# EEM_DIOT_connector.net
KiCad netlist of a schematic drawn in Altium Designer
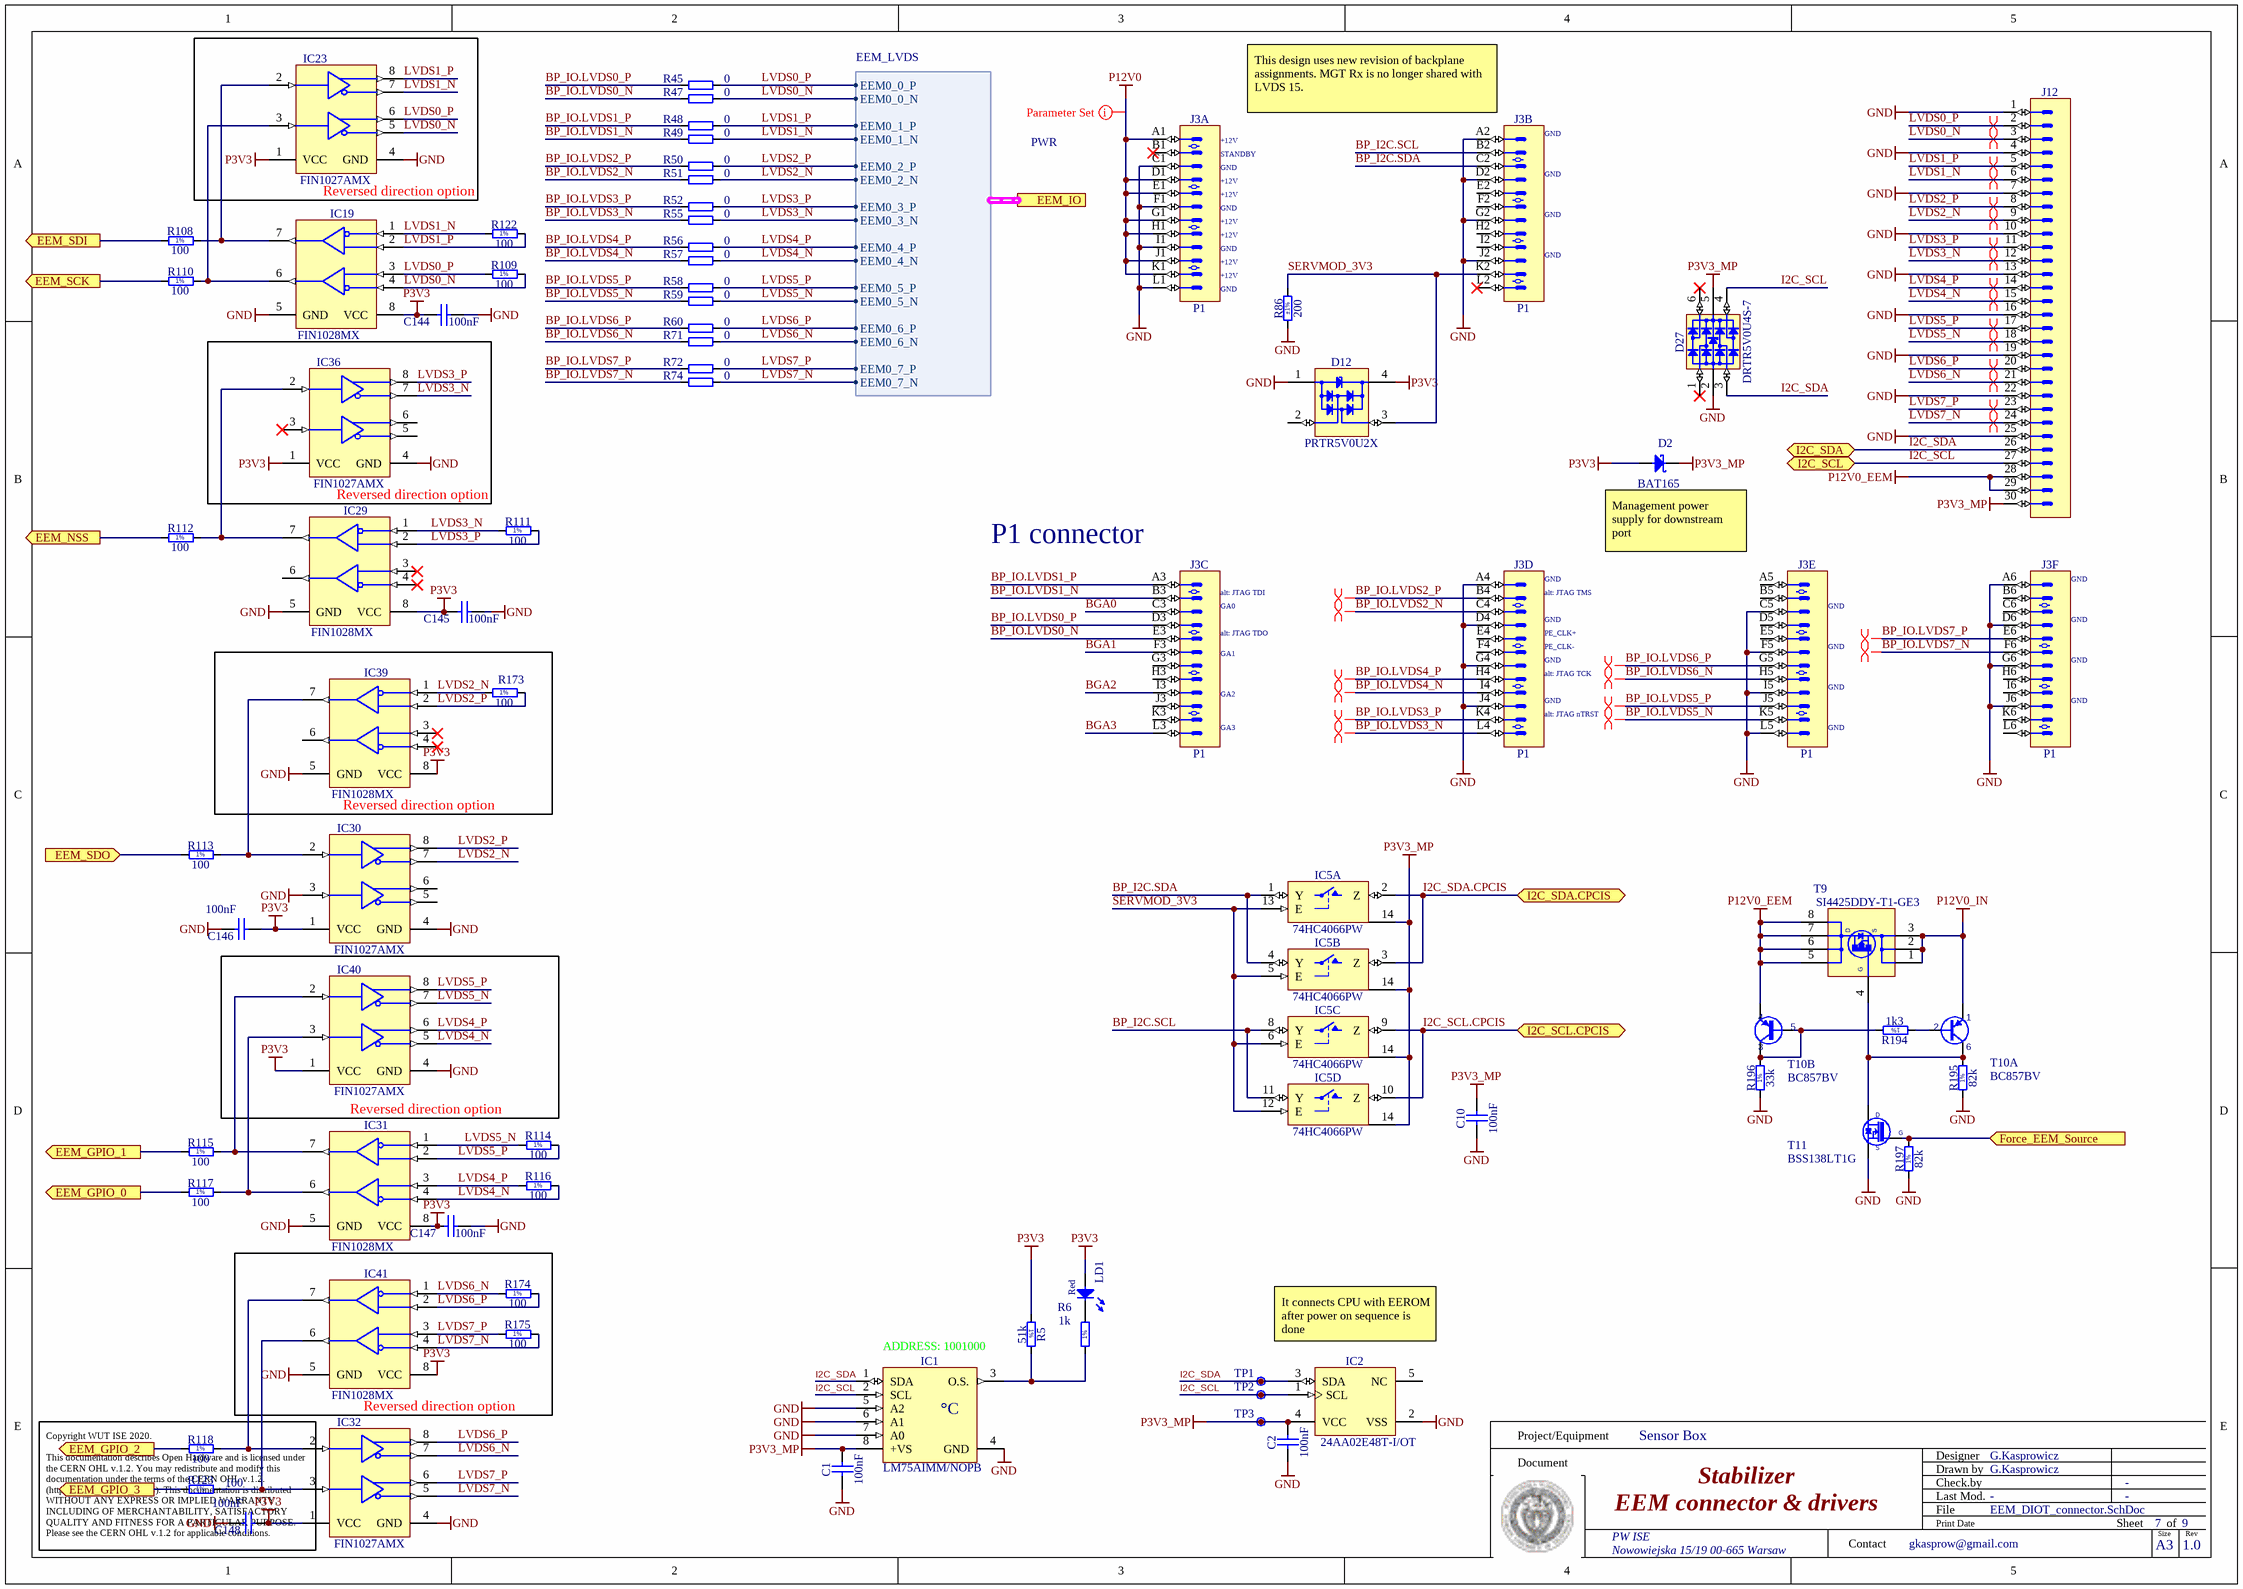
[diagram p0: EEM_DIOT_connector.SchDoc]

(export (version "E")
  (design (tool "Eeschema 10.0.6"))
  (components
    (comp (ref "C1")
      (value "100nF")
      (footprint "CAPC1005X55N")
      (description "Non-polarised capacitor")
      (fields (field (name "PART NUMBER") "CC0402_100NF_16V_10%_X5R") (field (name "VOLTAGE") "16V"))
      (libsource (lib "Capacitors") (part "Capacitor - non polarized"))
    )
    (comp (ref "C2")
      (value "100nF")
      (footprint "CAPC1005X55N")
      (description "Non-polarised capacitor")
      (fields (field (name "PART NUMBER") "CC0402_100NF_16V_10%_X5R") (field (name "VOLTAGE") "16V"))
      (libsource (lib "Capacitors") (part "Capacitor - non polarized"))
    )
    (comp (ref "C10")
      (value "100nF")
      (footprint "CAPC1608X87N")
      (description "Non-polarised capacitor")
      (fields (field (name "PART NUMBER") "CC0603_100NF_50V_10%_X7R") (field (name "VOLTAGE") "50V"))
      (libsource (lib "Capacitors") (part "Capacitor - non polarized"))
    )
    (comp (ref "C144")
      (value "100nF")
      (footprint "CAPC1005X55N")
      (description "Non-polarised capacitor")
      (fields (field (name "PART NUMBER") "CC0402_100NF_16V_10%_X5R") (field (name "VOLTAGE") "16V"))
      (libsource (lib "Capacitors") (part "Capacitor - non polarized"))
    )
    (comp (ref "C145")
      (value "100nF")
      (footprint "CAPC1005X55N")
      (description "Non-polarised capacitor")
      (fields (field (name "PART NUMBER") "CC0402_100NF_16V_10%_X5R") (field (name "VOLTAGE") "16V"))
      (libsource (lib "Capacitors") (part "Capacitor - non polarized"))
    )
    (comp (ref "C146")
      (value "100nF")
      (footprint "CAPC1005X55N")
      (description "Non-polarised capacitor")
      (fields (field (name "PART NUMBER") "CC0402_100NF_16V_10%_X5R") (field (name "VOLTAGE") "16V"))
      (libsource (lib "Capacitors") (part "Capacitor - non polarized"))
    )
    (comp (ref "C147")
      (value "100nF")
      (footprint "CAPC1005X55N")
      (description "Non-polarised capacitor")
      (fields (field (name "PART NUMBER") "CC0402_100NF_16V_10%_X5R") (field (name "VOLTAGE") "16V"))
      (libsource (lib "Capacitors") (part "Capacitor - non polarized"))
    )
    (comp (ref "C148")
      (value "100nF")
      (footprint "CAPC1005X55N")
      (description "Non-polarised capacitor")
      (fields (field (name "PART NUMBER") "CC0402_100NF_16V_10%_X5R") (field (name "VOLTAGE") "16V"))
      (libsource (lib "Capacitors") (part "Capacitor - non polarized"))
    )
    (comp (ref "D2")
      (value "BAT165")
      (footprint "SOD2512X110N")
      (description "Schottky Diode")
      (fields (field (name "VOLTAGE") "40V") (field (name "POWER") "750mA"))
      (libsource (lib "ICs And Semiconductors") (part "Diode Schottky"))
    )
    (comp (ref "D12")
      (value "PRTR5V0U2X")
      (footprint "SOT190P230X110-4N")
      (description "Ultra Low Capacitance Double Rail-to-Rail ESD Protection Diode")
      (fields (field (name "VOLTAGE") "5.5V") (field (name "MANUFACTURER") "NXP SEMICONDUCTORS"))
      (libsource (lib "ICs And Semiconductors") (part "PRTR5V0U2X"))
    )
    (comp (ref "D27")
      (value "DRTR5V0U4S-7")
      (footprint "SOT65P210X110-6N")
      (description "Integrated Quad Ultra-Low Capacitance ESD Protection")
      (fields (field (name "MANUFACTURER") "DIODES"))
      (libsource (lib "Diodes") (part "D_TVS_DRTR5V0U4S-7"))
    )
    (comp (ref "IC1")
      (value "LM75AIMM/NOPB")
      (footprint "SOP65P490X109-8N")
      (description "Digital Temperature Sensor and Thermal Watchdog with Two-Wire Interface")
      (fields (field (name "MANUFACTURER") "TEXAS INSTRUMENTS"))
      (libsource (lib "ICs And Semiconductors") (part "LM75"))
    )
    (comp (ref "IC2")
      (value "24AA02E48T-I/OT")
      (footprint "SOT95P280X145-5N")
      (description "1.7V-5.5V, 2K I2C Serial EEPROM With EUI-48 Node Identity")
      (fields (field (name "MANUFACTURER") "MICROCHIP TECHNOLOGY"))
      (libsource (lib "ICs And Semiconductors") (part "24AA02E48T-I/OT"))
    )
    (comp (ref "IC5")
      (value "74HC4066PW")
      (footprint "SOP65P640X110-14N")
      (fields (field (name "MANUFACTURER") "NXP SEMICONDUCTORS"))
      (libsource (lib "ICs And Semiconductors") (part "4066"))
    )
    (comp (ref "IC19")
      (value "FIN1028MX")
      (footprint "SOIC127P600X175-8N")
      (description "3.3V LVDS 2-Bit High-Speed Differential Reciever")
      (fields (field (name "MANUFACTURER") "ON Semiconductor"))
      (libsource (lib "LIBRARY_SCH") (part "IFC_FIN1028"))
    )
    (comp (ref "IC23")
      (value "FIN1027AMX")
      (footprint "SOIC127P600X175-8N")
      (description "3.3V LVDS, 2-Bit, High-Speed, Differential Driver")
      (fields (field (name "MANUFACTURER") "ON Semiconductor"))
      (libsource (lib "LIBRARY_SCH") (part "IFC_FIN1027A"))
    )
    (comp (ref "IC29")
      (value "FIN1028MX")
      (footprint "SOIC127P600X175-8N")
      (description "3.3V LVDS 2-Bit High-Speed Differential Reciever")
      (fields (field (name "MANUFACTURER") "ON Semiconductor"))
      (libsource (lib "LIBRARY_SCH") (part "IFC_FIN1028"))
    )
    (comp (ref "IC30")
      (value "FIN1027AMX")
      (footprint "SOIC127P600X175-8N")
      (description "3.3V LVDS, 2-Bit, High-Speed, Differential Driver")
      (fields (field (name "MANUFACTURER") "ON Semiconductor"))
      (libsource (lib "LIBRARY_SCH") (part "IFC_FIN1027A"))
    )
    (comp (ref "IC31")
      (value "FIN1028MX")
      (footprint "SOIC127P600X175-8N")
      (description "3.3V LVDS 2-Bit High-Speed Differential Reciever")
      (fields (field (name "MANUFACTURER") "ON Semiconductor"))
      (libsource (lib "LIBRARY_SCH") (part "IFC_FIN1028"))
    )
    (comp (ref "IC32")
      (value "FIN1027AMX")
      (footprint "SOIC127P600X175-8N")
      (description "3.3V LVDS, 2-Bit, High-Speed, Differential Driver")
      (fields (field (name "MANUFACTURER") "ON Semiconductor"))
      (libsource (lib "LIBRARY_SCH") (part "IFC_FIN1027A"))
    )
    (comp (ref "IC36")
      (value "FIN1027AMX")
      (footprint "SOIC127P600X175-8N")
      (description "3.3V LVDS, 2-Bit, High-Speed, Differential Driver")
      (fields (field (name "MANUFACTURER") "ON Semiconductor"))
      (libsource (lib "LIBRARY_SCH") (part "IFC_FIN1027A"))
    )
    (comp (ref "IC39")
      (value "FIN1028MX")
      (footprint "SOIC127P600X175-8N")
      (description "3.3V LVDS 2-Bit High-Speed Differential Reciever")
      (fields (field (name "MANUFACTURER") "ON Semiconductor"))
      (libsource (lib "LIBRARY_SCH") (part "IFC_FIN1028"))
    )
    (comp (ref "IC40")
      (value "FIN1027AMX")
      (footprint "SOIC127P600X175-8N")
      (description "3.3V LVDS, 2-Bit, High-Speed, Differential Driver")
      (fields (field (name "MANUFACTURER") "ON Semiconductor"))
      (libsource (lib "LIBRARY_SCH") (part "IFC_FIN1027A"))
    )
    (comp (ref "IC41")
      (value "FIN1028MX")
      (footprint "SOIC127P600X175-8N")
      (description "3.3V LVDS 2-Bit High-Speed Differential Reciever")
      (fields (field (name "MANUFACTURER") "ON Semiconductor"))
      (libsource (lib "LIBRARY_SCH") (part "IFC_FIN1028"))
    )
    (comp (ref "J3")
      (value "P1")
      (footprint "AMPHENOL_10052825-101LF")
      (description "72 Contacts Header, 6 Columns, 4 Pairs per Column")
      (fields (field (name "PART NUMBER") "AMPHENOL_10052825-101LF") (field (name "MANUFACTURER") "AMPHENOL"))
      (libsource (lib "Connectors") (part "AMPHENOL_10052825-101LF"))
    )
    (comp (ref "J12")
      (value "~")
      (footprint "3M_N2530-6002RB")
      (description "Connector 30 Male")
      (fields (field (name "PART NUMBER") "3M_N2530-6002RB") (field (name "MANUFACTURER") "3M"))
      (libsource (lib "Connectors") (part "Connector 30 Male"))
    )
    (comp (ref "LD1")
      (value "Red")
      (footprint "LED_KINGBRIGHT_KPH-1608SURCK")
      (description "LED Red 1C 2A")
      (fields
        (field (name "PART NUMBER") "LED_KINGBRIGHT_KPH-1608SURCK")
        (field (name "MANUFACTURER") "KINGBRIGHT")
      )
      (libsource (lib "ICs And Semiconductors") (part "LED Red 1C 2A"))
    )
    (comp (ref "R5")
      (value "51k")
      (footprint "RESC1005X40N")
      (description "Resistor - 1%")
      (fields (field (name "PART NUMBER") "R0402_51K_1%_0.0625W_100PPM") (field (name "POWER") "0.0625W"))
      (libsource (lib "Resistors") (part "Resistor - 1%"))
    )
    (comp (ref "R6")
      (value "1k")
      (footprint "RESC1005X40N")
      (description "Resistor - 1%")
      (fields (field (name "PART NUMBER") "R0402_1K_1%_0.0625W_100PPM") (field (name "POWER") "0.0625W"))
      (libsource (lib "Resistors") (part "Resistor - 1%"))
    )
    (comp (ref "R45")
      (value "0")
      (footprint "RESC1608X55N")
      (description "Resistor")
      (fields (field (name "PART NUMBER") "R0603_0R_JUMPER") (field (name "MANUFACTURER") "GENERIC"))
      (libsource (lib "Resistors") (part "Resistor"))
    )
    (comp (ref "R47")
      (value "0")
      (footprint "RESC1608X55N")
      (description "Resistor")
      (fields (field (name "PART NUMBER") "R0603_0R_JUMPER") (field (name "MANUFACTURER") "GENERIC"))
      (libsource (lib "Resistors") (part "Resistor"))
    )
    (comp (ref "R48")
      (value "0")
      (footprint "RESC1608X55N")
      (description "Resistor")
      (fields (field (name "PART NUMBER") "R0603_0R_JUMPER") (field (name "MANUFACTURER") "GENERIC"))
      (libsource (lib "Resistors") (part "Resistor"))
    )
    (comp (ref "R49")
      (value "0")
      (footprint "RESC1608X55N")
      (description "Resistor")
      (fields (field (name "PART NUMBER") "R0603_0R_JUMPER") (field (name "MANUFACTURER") "GENERIC"))
      (libsource (lib "Resistors") (part "Resistor"))
    )
    (comp (ref "R50")
      (value "0")
      (footprint "RESC1608X55N")
      (description "Resistor")
      (fields (field (name "PART NUMBER") "R0603_0R_JUMPER") (field (name "MANUFACTURER") "GENERIC"))
      (libsource (lib "Resistors") (part "Resistor"))
    )
    (comp (ref "R51")
      (value "0")
      (footprint "RESC1608X55N")
      (description "Resistor")
      (fields (field (name "PART NUMBER") "R0603_0R_JUMPER") (field (name "MANUFACTURER") "GENERIC"))
      (libsource (lib "Resistors") (part "Resistor"))
    )
    (comp (ref "R52")
      (value "0")
      (footprint "RESC1608X55N")
      (description "Resistor")
      (fields (field (name "PART NUMBER") "R0603_0R_JUMPER") (field (name "MANUFACTURER") "GENERIC"))
      (libsource (lib "Resistors") (part "Resistor"))
    )
    (comp (ref "R55")
      (value "0")
      (footprint "RESC1608X55N")
      (description "Resistor")
      (fields (field (name "PART NUMBER") "R0603_0R_JUMPER") (field (name "MANUFACTURER") "GENERIC"))
      (libsource (lib "Resistors") (part "Resistor"))
    )
    (comp (ref "R56")
      (value "0")
      (footprint "RESC1608X55N")
      (description "Resistor")
      (fields (field (name "PART NUMBER") "R0603_0R_JUMPER") (field (name "MANUFACTURER") "GENERIC"))
      (libsource (lib "Resistors") (part "Resistor"))
    )
    (comp (ref "R57")
      (value "0")
      (footprint "RESC1608X55N")
      (description "Resistor")
      (fields (field (name "PART NUMBER") "R0603_0R_JUMPER") (field (name "MANUFACTURER") "GENERIC"))
      (libsource (lib "Resistors") (part "Resistor"))
    )
    (comp (ref "R58")
      (value "0")
      (footprint "RESC1608X55N")
      (description "Resistor")
      (fields (field (name "PART NUMBER") "R0603_0R_JUMPER") (field (name "MANUFACTURER") "GENERIC"))
      (libsource (lib "Resistors") (part "Resistor"))
    )
    (comp (ref "R59")
      (value "0")
      (footprint "RESC1608X55N")
      (description "Resistor")
      (fields (field (name "PART NUMBER") "R0603_0R_JUMPER") (field (name "MANUFACTURER") "GENERIC"))
      (libsource (lib "Resistors") (part "Resistor"))
    )
    (comp (ref "R60")
      (value "0")
      (footprint "RESC1608X55N")
      (description "Resistor")
      (fields (field (name "PART NUMBER") "R0603_0R_JUMPER") (field (name "MANUFACTURER") "GENERIC"))
      (libsource (lib "Resistors") (part "Resistor"))
    )
    (comp (ref "R71")
      (value "0")
      (footprint "RESC1608X55N")
      (description "Resistor")
      (fields (field (name "PART NUMBER") "R0603_0R_JUMPER") (field (name "MANUFACTURER") "GENERIC"))
      (libsource (lib "Resistors") (part "Resistor"))
    )
    (comp (ref "R72")
      (value "0")
      (footprint "RESC1608X55N")
      (description "Resistor")
      (fields (field (name "PART NUMBER") "R0603_0R_JUMPER") (field (name "MANUFACTURER") "GENERIC"))
      (libsource (lib "Resistors") (part "Resistor"))
    )
    (comp (ref "R74")
      (value "0")
      (footprint "RESC1608X55N")
      (description "Resistor")
      (fields (field (name "PART NUMBER") "R0603_0R_JUMPER") (field (name "MANUFACTURER") "GENERIC"))
      (libsource (lib "Resistors") (part "Resistor"))
    )
    (comp (ref "R86")
      (value "200")
      (footprint "RESC1608X55N")
      (description "Resistor - 1%")
      (fields
        (field (name "TOLERANCE") "±1%")
        (field (name "PART NUMBER") "R0603_200R_1%_0.1W_100PPM")
        (field (name "POWER") "0.1W")
      )
      (libsource (lib "") (part "Resistor - 1%_1"))
    )
    (comp (ref "R108")
      (value "100")
      (footprint "RESC1005X40N")
      (description "Resistor - 1%")
      (fields (field (name "PART NUMBER") "R0402_100R_1%_0.0625W_100PPM") (field (name "POWER") "0.0625W"))
      (libsource (lib "Resistors") (part "Resistor - 1%"))
    )
    (comp (ref "R109")
      (value "100")
      (footprint "RESC1005X40N")
      (description "Resistor - 1%")
      (fields (field (name "PART NUMBER") "R0402_100R_1%_0.0625W_100PPM") (field (name "POWER") "0.0625W"))
      (libsource (lib "Resistors") (part "Resistor - 1%"))
    )
    (comp (ref "R110")
      (value "100")
      (footprint "RESC1005X40N")
      (description "Resistor - 1%")
      (fields (field (name "PART NUMBER") "R0402_100R_1%_0.0625W_100PPM") (field (name "POWER") "0.0625W"))
      (libsource (lib "Resistors") (part "Resistor - 1%"))
    )
    (comp (ref "R111")
      (value "100")
      (footprint "RESC1005X40N")
      (description "Resistor - 1%")
      (fields (field (name "PART NUMBER") "R0402_100R_1%_0.0625W_100PPM") (field (name "POWER") "0.0625W"))
      (libsource (lib "Resistors") (part "Resistor - 1%"))
    )
    (comp (ref "R112")
      (value "100")
      (footprint "RESC1005X40N")
      (description "Resistor - 1%")
      (fields (field (name "PART NUMBER") "R0402_100R_1%_0.0625W_100PPM") (field (name "POWER") "0.0625W"))
      (libsource (lib "Resistors") (part "Resistor - 1%"))
    )
    (comp (ref "R113")
      (value "100")
      (footprint "RESC1005X40N")
      (description "Resistor - 1%")
      (fields (field (name "PART NUMBER") "R0402_100R_1%_0.0625W_100PPM") (field (name "POWER") "0.0625W"))
      (libsource (lib "Resistors") (part "Resistor - 1%"))
    )
    (comp (ref "R114")
      (value "100")
      (footprint "RESC1005X40N")
      (description "Resistor - 1%")
      (fields (field (name "PART NUMBER") "R0402_100R_1%_0.0625W_100PPM") (field (name "POWER") "0.0625W"))
      (libsource (lib "Resistors") (part "Resistor - 1%"))
    )
    (comp (ref "R115")
      (value "100")
      (footprint "RESC1005X40N")
      (description "Resistor - 1%")
      (fields (field (name "PART NUMBER") "R0402_100R_1%_0.0625W_100PPM") (field (name "POWER") "0.0625W"))
      (libsource (lib "Resistors") (part "Resistor - 1%"))
    )
    (comp (ref "R116")
      (value "100")
      (footprint "RESC1005X40N")
      (description "Resistor - 1%")
      (fields (field (name "PART NUMBER") "R0402_100R_1%_0.0625W_100PPM") (field (name "POWER") "0.0625W"))
      (libsource (lib "Resistors") (part "Resistor - 1%"))
    )
    (comp (ref "R117")
      (value "100")
      (footprint "RESC1005X40N")
      (description "Resistor - 1%")
      (fields (field (name "PART NUMBER") "R0402_100R_1%_0.0625W_100PPM") (field (name "POWER") "0.0625W"))
      (libsource (lib "Resistors") (part "Resistor - 1%"))
    )
    (comp (ref "R118")
      (value "100")
      (footprint "RESC1005X40N")
      (description "Resistor - 1%")
      (fields (field (name "PART NUMBER") "R0402_100R_1%_0.0625W_100PPM") (field (name "POWER") "0.0625W"))
      (libsource (lib "Resistors") (part "Resistor - 1%"))
    )
    (comp (ref "R122")
      (value "100")
      (footprint "RESC1005X40N")
      (description "Resistor - 1%")
      (fields (field (name "PART NUMBER") "R0402_100R_1%_0.0625W_100PPM") (field (name "POWER") "0.0625W"))
      (libsource (lib "Resistors") (part "Resistor - 1%"))
    )
    (comp (ref "R123")
      (value "100")
      (footprint "RESC1005X40N")
      (description "Resistor - 1%")
      (fields (field (name "PART NUMBER") "R0402_100R_1%_0.0625W_100PPM") (field (name "POWER") "0.0625W"))
      (libsource (lib "Resistors") (part "Resistor - 1%"))
    )
    (comp (ref "R173")
      (value "100")
      (footprint "RESC1005X40N")
      (description "Resistor - 1%")
      (fields (field (name "PART NUMBER") "R0402_100R_1%_0.0625W_100PPM") (field (name "POWER") "0.0625W"))
      (libsource (lib "Resistors") (part "Resistor - 1%"))
    )
    (comp (ref "R174")
      (value "100")
      (footprint "RESC1005X40N")
      (description "Resistor - 1%")
      (fields (field (name "PART NUMBER") "R0402_100R_1%_0.0625W_100PPM") (field (name "POWER") "0.0625W"))
      (libsource (lib "Resistors") (part "Resistor - 1%"))
    )
    (comp (ref "R175")
      (value "100")
      (footprint "RESC1005X40N")
      (description "Resistor - 1%")
      (fields (field (name "PART NUMBER") "R0402_100R_1%_0.0625W_100PPM") (field (name "POWER") "0.0625W"))
      (libsource (lib "Resistors") (part "Resistor - 1%"))
    )
    (comp (ref "R194")
      (value "1k3")
      (footprint "RESC1608X55N")
      (description "Resistor - 1%")
      (fields (field (name "PART NUMBER") "R0603_1K3_1%_0.1W_100PPM") (field (name "POWER") "0.1W"))
      (libsource (lib "Resistors") (part "Resistor - 1%"))
    )
    (comp (ref "R195")
      (value "82k")
      (footprint "RESC1608X55N")
      (description "Resistor - 1%")
      (fields (field (name "PART NUMBER") "R0603_82K_1%_0.1W_100PPM") (field (name "POWER") "0.1W"))
      (libsource (lib "Resistors") (part "Resistor - 1%"))
    )
    (comp (ref "R196")
      (value "33k")
      (footprint "RESC1005X40N")
      (description "Resistor - 1%")
      (fields (field (name "PART NUMBER") "R0402_33K_1%_0.0625W_100PPM") (field (name "POWER") "0.0625W"))
      (libsource (lib "Resistors") (part "Resistor - 1%"))
    )
    (comp (ref "R197")
      (value "82k")
      (footprint "RESC1608X55N")
      (description "Resistor - 1%")
      (fields (field (name "PART NUMBER") "R0603_82K_1%_0.1W_100PPM") (field (name "POWER") "0.1W"))
      (libsource (lib "Resistors") (part "Resistor - 1%"))
    )
    (comp (ref "T9")
      (value "SI4425DDY-T1-GE3")
      (footprint "SOIC127P600X175-8N")
      (description "-30V -19.7A P-Channel MOSFET")
      (fields (field (name "MANUFACTURER") "VISHAY SILICONIX"))
      (libsource (lib "ICs And Semiconductors") (part "SI4425DDY"))
    )
    (comp (ref "T10")
      (value "BC857BV")
      (footprint "SOTFL50P160X60-6N")
      (description "45V, 100mA PNP General Purpose Double Transistor")
      (fields (field (name "MANUFACTURER") "NXP SEMICONDUCTORS"))
      (libsource (lib "ICs And Semiconductors") (part "BC857BV"))
    )
    (comp (ref "T11")
      (value "BSS138LT1G")
      (footprint "SOT95P240X110-3N")
      (description "N-CHANNEL MOSFET WITH DIODE")
      (fields (field (name "MANUFACTURER") "ON SEMICONDUCTOR"))
      (libsource (lib "ICs And Semiconductors") (part "N-MOSFET-D 1G 2S 3D"))
    )
    (comp (ref "TP1")
      (value "Test Point")
      (footprint "TPS127")
      (fields (field (name "PART NUMBER") "SMD_PAD_1.27X1.27MM"))
      (libsource (lib "Eletro-mechanical") (part "Test Point"))
    )
    (comp (ref "TP2")
      (value "Test Point")
      (footprint "TPS127")
      (fields (field (name "PART NUMBER") "SMD_PAD_1.27X1.27MM"))
      (libsource (lib "Eletro-mechanical") (part "Test Point"))
    )
    (comp (ref "TP3")
      (value "Test Point")
      (footprint "TPS127")
      (fields (field (name "PART NUMBER") "SMD_PAD_1.27X1.27MM"))
      (libsource (lib "Eletro-mechanical") (part "Test Point"))
    )
  )
  (nets
    (net (code "2") (name "/BGA0") (class "Default")
      (node (ref "J3") (pin "C3") (pinfunction "C3_C3") (pintype "bidirectional"))
    )
    (net (code "3") (name "/BGA1") (class "Default")
      (node (ref "J3") (pin "F3") (pinfunction "F3_F3") (pintype "bidirectional"))
    )
    (net (code "4") (name "/BGA2") (class "Default")
      (node (ref "J3") (pin "I3") (pinfunction "I3_I3") (pintype "bidirectional"))
    )
    (net (code "5") (name "/BGA3") (class "Default")
      (node (ref "J3") (pin "L3") (pinfunction "L3_L3") (pintype "bidirectional"))
    )
    (net (code "6") (name "/BP_I2C.SCL") (class "Default")
      (node (ref "IC5") (pin "11") (pinfunction "Y_11") (pintype "bidirectional"))
      (node (ref "IC5") (pin "8") (pinfunction "Y_8") (pintype "bidirectional"))
      (node (ref "J3") (pin "B2") (pinfunction "B2_B2") (pintype "bidirectional"))
    )
    (net (code "7") (name "/BP_I2C.SDA") (class "Default")
      (node (ref "IC5") (pin "1") (pinfunction "Y_1") (pintype "bidirectional"))
      (node (ref "IC5") (pin "4") (pinfunction "Y_4") (pintype "bidirectional"))
      (node (ref "J3") (pin "C2") (pinfunction "C2_C2") (pintype "bidirectional"))
    )
    (net (code "8") (name "/BP_IO.LVDS0_N") (class "Default")
      (node (ref "J3") (pin "E3") (pinfunction "E3_E3") (pintype "bidirectional"))
      (node (ref "R47") (pin "1") (pinfunction "1_1") (pintype "passive"))
    )
    (net (code "9") (name "/BP_IO.LVDS0_P") (class "Default")
      (node (ref "J3") (pin "D3") (pinfunction "D3_D3") (pintype "bidirectional"))
      (node (ref "R45") (pin "1") (pinfunction "1_1") (pintype "passive"))
    )
    (net (code "10") (name "/BP_IO.LVDS1_N") (class "Default")
      (node (ref "J3") (pin "B3") (pinfunction "B3_B3") (pintype "bidirectional"))
      (node (ref "R49") (pin "1") (pinfunction "1_1") (pintype "passive"))
    )
    (net (code "11") (name "/BP_IO.LVDS1_P") (class "Default")
      (node (ref "J3") (pin "A3") (pinfunction "A3_A3") (pintype "bidirectional"))
      (node (ref "R48") (pin "1") (pinfunction "1_1") (pintype "passive"))
    )
    (net (code "12") (name "/BP_IO.LVDS2_N") (class "Default")
      (node (ref "J3") (pin "C4") (pinfunction "C4_C4") (pintype "bidirectional"))
      (node (ref "R51") (pin "1") (pinfunction "1_1") (pintype "passive"))
    )
    (net (code "13") (name "/BP_IO.LVDS2_P") (class "Default")
      (node (ref "J3") (pin "B4") (pinfunction "B4_B4") (pintype "bidirectional"))
      (node (ref "R50") (pin "1") (pinfunction "1_1") (pintype "passive"))
    )
    (net (code "14") (name "/BP_IO.LVDS3_N") (class "Default")
      (node (ref "J3") (pin "L4") (pinfunction "L4_L4") (pintype "bidirectional"))
      (node (ref "R55") (pin "1") (pinfunction "1_1") (pintype "passive"))
    )
    (net (code "15") (name "/BP_IO.LVDS3_P") (class "Default")
      (node (ref "J3") (pin "K4") (pinfunction "K4_K4") (pintype "bidirectional"))
      (node (ref "R52") (pin "1") (pinfunction "1_1") (pintype "passive"))
    )
    (net (code "16") (name "/BP_IO.LVDS4_N") (class "Default")
      (node (ref "J3") (pin "I4") (pinfunction "I4_I4") (pintype "bidirectional"))
      (node (ref "R57") (pin "1") (pinfunction "1_1") (pintype "passive"))
    )
    (net (code "17") (name "/BP_IO.LVDS4_P") (class "Default")
      (node (ref "J3") (pin "H4") (pinfunction "H4_H4") (pintype "bidirectional"))
      (node (ref "R56") (pin "1") (pinfunction "1_1") (pintype "passive"))
    )
    (net (code "18") (name "/BP_IO.LVDS5_N") (class "Default")
      (node (ref "J3") (pin "K5") (pinfunction "K5_K5") (pintype "bidirectional"))
      (node (ref "R59") (pin "1") (pinfunction "1_1") (pintype "passive"))
    )
    (net (code "19") (name "/BP_IO.LVDS5_P") (class "Default")
      (node (ref "J3") (pin "J5") (pinfunction "J5_J5") (pintype "bidirectional"))
      (node (ref "R58") (pin "1") (pinfunction "1_1") (pintype "passive"))
    )
    (net (code "20") (name "/BP_IO.LVDS6_N") (class "Default")
      (node (ref "J3") (pin "H5") (pinfunction "H5_H5") (pintype "bidirectional"))
      (node (ref "R71") (pin "1") (pinfunction "1_1") (pintype "passive"))
    )
    (net (code "21") (name "/BP_IO.LVDS6_P") (class "Default")
      (node (ref "J3") (pin "G5") (pinfunction "G5_G5") (pintype "bidirectional"))
      (node (ref "R60") (pin "1") (pinfunction "1_1") (pintype "passive"))
    )
    (net (code "22") (name "/BP_IO.LVDS7_N") (class "Default")
      (node (ref "J3") (pin "F6") (pinfunction "F6_F6") (pintype "bidirectional"))
      (node (ref "R74") (pin "1") (pinfunction "1_1") (pintype "passive"))
    )
    (net (code "23") (name "/BP_IO.LVDS7_P") (class "Default")
      (node (ref "J3") (pin "E6") (pinfunction "E6_E6") (pintype "bidirectional"))
      (node (ref "R72") (pin "1") (pinfunction "1_1") (pintype "passive"))
    )
    (net (code "24") (name "/EEM_GPIO_0") (class "Default")
      (node (ref "R117") (pin "1") (pinfunction "1_1") (pintype "passive"))
    )
    (net (code "25") (name "/EEM_GPIO_1") (class "Default")
      (node (ref "R115") (pin "1") (pinfunction "1_1") (pintype "passive"))
    )
    (net (code "26") (name "/EEM_GPIO_2") (class "Default")
      (node (ref "R118") (pin "1") (pinfunction "1_1") (pintype "passive"))
    )
    (net (code "27") (name "/EEM_GPIO_3") (class "Default")
      (node (ref "R123") (pin "1") (pinfunction "1_1") (pintype "passive"))
    )
    (net (code "28") (name "/EEM_NSS") (class "Default")
      (node (ref "R112") (pin "1") (pinfunction "1_1") (pintype "passive"))
    )
    (net (code "29") (name "/EEM_SCK") (class "Default")
      (node (ref "R110") (pin "1") (pinfunction "1_1") (pintype "passive"))
    )
    (net (code "30") (name "/EEM_SDI") (class "Default")
      (node (ref "R108") (pin "1") (pinfunction "1_1") (pintype "passive"))
    )
    (net (code "31") (name "/EEM_SDO") (class "Default")
      (node (ref "R113") (pin "1") (pinfunction "1_1") (pintype "passive"))
    )
    (net (code "32") (name "/Force_EEM_Source") (class "Default")
      (node (ref "R197") (pin "2") (pinfunction "2_2") (pintype "passive"))
      (node (ref "T11") (pin "1") (pinfunction "G_1") (pintype "passive"))
    )
    (net (code "33") (name "/I2C_SCL") (class "Default")
      (node (ref "D27") (pin "4") (pinfunction "I/O3_4") (pintype "bidirectional"))
      (node (ref "IC1") (pin "2") (pinfunction "SCL_2") (pintype "input"))
      (node (ref "IC2") (pin "1") (pinfunction "SCL_1") (pintype "input"))
      (node (ref "J12") (pin "27") (pinfunction "27_27") (pintype "bidirectional"))
      (node (ref "TP2") (pin "1") (pinfunction "1_1") (pintype "bidirectional"))
    )
    (net (code "34") (name "/I2C_SCL.CPCIS") (class "Default")
      (node (ref "IC5") (pin "10") (pinfunction "Z_10") (pintype "bidirectional"))
      (node (ref "IC5") (pin "9") (pinfunction "Z_9") (pintype "bidirectional"))
    )
    (net (code "35") (name "/I2C_SDA") (class "Default")
      (node (ref "D27") (pin "3") (pinfunction "I/O2_3") (pintype "bidirectional"))
      (node (ref "IC1") (pin "1") (pinfunction "SDA_1") (pintype "bidirectional"))
      (node (ref "IC2") (pin "3") (pinfunction "SDA_3") (pintype "bidirectional"))
      (node (ref "J12") (pin "26") (pinfunction "26_26") (pintype "bidirectional"))
      (node (ref "TP1") (pin "1") (pinfunction "1_1") (pintype "bidirectional"))
    )
    (net (code "36") (name "/I2C_SDA.CPCIS") (class "Default")
      (node (ref "IC5") (pin "2") (pinfunction "Z_2") (pintype "bidirectional"))
      (node (ref "IC5") (pin "3") (pinfunction "Z_3") (pintype "bidirectional"))
    )
    (net (code "37") (name "/LVDS0_N") (class "Default")
      (node (ref "IC19") (pin "4") (pinfunction "RIN2-_4") (pintype "input"))
      (node (ref "IC23") (pin "5") (pinfunction "DOUT-_5") (pintype "output"))
      (node (ref "J12") (pin "3") (pinfunction "3_3") (pintype "bidirectional"))
      (node (ref "R109") (pin "2") (pinfunction "2_2") (pintype "passive"))
      (node (ref "R47") (pin "2") (pinfunction "2_2") (pintype "passive"))
    )
    (net (code "38") (name "/LVDS0_P") (class "Default")
      (node (ref "IC19") (pin "3") (pinfunction "RIN2+_3") (pintype "input"))
      (node (ref "IC23") (pin "6") (pinfunction "DOUT+_6") (pintype "output"))
      (node (ref "J12") (pin "2") (pinfunction "2_2") (pintype "bidirectional"))
      (node (ref "R109") (pin "1") (pinfunction "1_1") (pintype "passive"))
      (node (ref "R45") (pin "2") (pinfunction "2_2") (pintype "passive"))
    )
    (net (code "39") (name "/LVDS1_N") (class "Default")
      (node (ref "IC19") (pin "1") (pinfunction "RIN1-_1") (pintype "input"))
      (node (ref "IC23") (pin "7") (pinfunction "DOUT-_7") (pintype "output"))
      (node (ref "J12") (pin "6") (pinfunction "6_6") (pintype "bidirectional"))
      (node (ref "R122") (pin "1") (pinfunction "1_1") (pintype "passive"))
      (node (ref "R49") (pin "2") (pinfunction "2_2") (pintype "passive"))
    )
    (net (code "40") (name "/LVDS1_P") (class "Default")
      (node (ref "IC19") (pin "2") (pinfunction "RIN1+_2") (pintype "input"))
      (node (ref "IC23") (pin "8") (pinfunction "DOUT+_8") (pintype "output"))
      (node (ref "J12") (pin "5") (pinfunction "5_5") (pintype "bidirectional"))
      (node (ref "R122") (pin "2") (pinfunction "2_2") (pintype "passive"))
      (node (ref "R48") (pin "2") (pinfunction "2_2") (pintype "passive"))
    )
    (net (code "41") (name "/LVDS2_N") (class "Default")
      (node (ref "IC30") (pin "7") (pinfunction "DOUT-_7") (pintype "output"))
      (node (ref "IC39") (pin "1") (pinfunction "RIN1-_1") (pintype "input"))
      (node (ref "J12") (pin "9") (pinfunction "9_9") (pintype "bidirectional"))
      (node (ref "R173") (pin "1") (pinfunction "1_1") (pintype "passive"))
      (node (ref "R51") (pin "2") (pinfunction "2_2") (pintype "passive"))
    )
    (net (code "42") (name "/LVDS2_P") (class "Default")
      (node (ref "IC30") (pin "8") (pinfunction "DOUT+_8") (pintype "output"))
      (node (ref "IC39") (pin "2") (pinfunction "RIN1+_2") (pintype "input"))
      (node (ref "J12") (pin "8") (pinfunction "8_8") (pintype "bidirectional"))
      (node (ref "R173") (pin "2") (pinfunction "2_2") (pintype "passive"))
      (node (ref "R50") (pin "2") (pinfunction "2_2") (pintype "passive"))
    )
    (net (code "43") (name "/LVDS3_N") (class "Default")
      (node (ref "IC29") (pin "1") (pinfunction "RIN1-_1") (pintype "input"))
      (node (ref "IC36") (pin "7") (pinfunction "DOUT-_7") (pintype "output"))
      (node (ref "J12") (pin "12") (pinfunction "12_12") (pintype "bidirectional"))
      (node (ref "R111") (pin "1") (pinfunction "1_1") (pintype "passive"))
      (node (ref "R55") (pin "2") (pinfunction "2_2") (pintype "passive"))
    )
    (net (code "44") (name "/LVDS3_P") (class "Default")
      (node (ref "IC29") (pin "2") (pinfunction "RIN1+_2") (pintype "input"))
      (node (ref "IC36") (pin "8") (pinfunction "DOUT+_8") (pintype "output"))
      (node (ref "J12") (pin "11") (pinfunction "11_11") (pintype "bidirectional"))
      (node (ref "R111") (pin "2") (pinfunction "2_2") (pintype "passive"))
      (node (ref "R52") (pin "2") (pinfunction "2_2") (pintype "passive"))
    )
    (net (code "45") (name "/LVDS4_N") (class "Default")
      (node (ref "IC31") (pin "4") (pinfunction "RIN2-_4") (pintype "input"))
      (node (ref "IC40") (pin "5") (pinfunction "DOUT-_5") (pintype "output"))
      (node (ref "J12") (pin "15") (pinfunction "15_15") (pintype "bidirectional"))
      (node (ref "R116") (pin "2") (pinfunction "2_2") (pintype "passive"))
      (node (ref "R57") (pin "2") (pinfunction "2_2") (pintype "passive"))
    )
    (net (code "46") (name "/LVDS4_P") (class "Default")
      (node (ref "IC31") (pin "3") (pinfunction "RIN2+_3") (pintype "input"))
      (node (ref "IC40") (pin "6") (pinfunction "DOUT+_6") (pintype "output"))
      (node (ref "J12") (pin "14") (pinfunction "14_14") (pintype "bidirectional"))
      (node (ref "R116") (pin "1") (pinfunction "1_1") (pintype "passive"))
      (node (ref "R56") (pin "2") (pinfunction "2_2") (pintype "passive"))
    )
    (net (code "47") (name "/LVDS5_N") (class "Default")
      (node (ref "IC31") (pin "1") (pinfunction "RIN1-_1") (pintype "input"))
      (node (ref "IC40") (pin "7") (pinfunction "DOUT-_7") (pintype "output"))
      (node (ref "J12") (pin "18") (pinfunction "18_18") (pintype "bidirectional"))
      (node (ref "R114") (pin "1") (pinfunction "1_1") (pintype "passive"))
      (node (ref "R59") (pin "2") (pinfunction "2_2") (pintype "passive"))
    )
    (net (code "48") (name "/LVDS5_P") (class "Default")
      (node (ref "IC31") (pin "2") (pinfunction "RIN1+_2") (pintype "input"))
      (node (ref "IC40") (pin "8") (pinfunction "DOUT+_8") (pintype "output"))
      (node (ref "J12") (pin "17") (pinfunction "17_17") (pintype "bidirectional"))
      (node (ref "R114") (pin "2") (pinfunction "2_2") (pintype "passive"))
      (node (ref "R58") (pin "2") (pinfunction "2_2") (pintype "passive"))
    )
    (net (code "49") (name "/LVDS6_N") (class "Default")
      (node (ref "IC32") (pin "7") (pinfunction "DOUT-_7") (pintype "output"))
      (node (ref "IC41") (pin "1") (pinfunction "RIN1-_1") (pintype "input"))
      (node (ref "J12") (pin "21") (pinfunction "21_21") (pintype "bidirectional"))
      (node (ref "R174") (pin "1") (pinfunction "1_1") (pintype "passive"))
      (node (ref "R71") (pin "2") (pinfunction "2_2") (pintype "passive"))
    )
    (net (code "50") (name "/LVDS6_P") (class "Default")
      (node (ref "IC32") (pin "8") (pinfunction "DOUT+_8") (pintype "output"))
      (node (ref "IC41") (pin "2") (pinfunction "RIN1+_2") (pintype "input"))
      (node (ref "J12") (pin "20") (pinfunction "20_20") (pintype "bidirectional"))
      (node (ref "R174") (pin "2") (pinfunction "2_2") (pintype "passive"))
      (node (ref "R60") (pin "2") (pinfunction "2_2") (pintype "passive"))
    )
    (net (code "51") (name "/LVDS7_N") (class "Default")
      (node (ref "IC32") (pin "5") (pinfunction "DOUT-_5") (pintype "output"))
      (node (ref "IC41") (pin "4") (pinfunction "RIN2-_4") (pintype "input"))
      (node (ref "J12") (pin "24") (pinfunction "24_24") (pintype "bidirectional"))
      (node (ref "R175") (pin "2") (pinfunction "2_2") (pintype "passive"))
      (node (ref "R74") (pin "2") (pinfunction "2_2") (pintype "passive"))
    )
    (net (code "52") (name "/LVDS7_P") (class "Default")
      (node (ref "IC32") (pin "6") (pinfunction "DOUT+_6") (pintype "output"))
      (node (ref "IC41") (pin "3") (pinfunction "RIN2+_3") (pintype "input"))
      (node (ref "J12") (pin "23") (pinfunction "23_23") (pintype "bidirectional"))
      (node (ref "R175") (pin "1") (pinfunction "1_1") (pintype "passive"))
      (node (ref "R72") (pin "2") (pinfunction "2_2") (pintype "passive"))
    )
    (net (code "53") (name "/SERVMOD_3V3") (class "Default")
      (node (ref "D12") (pin "3") (pinfunction "I/O2_3") (pintype "bidirectional"))
      (node (ref "IC5") (pin "12") (pinfunction "E_12") (pintype "input"))
      (node (ref "IC5") (pin "13") (pinfunction "E_13") (pintype "input"))
      (node (ref "IC5") (pin "5") (pinfunction "E_5") (pintype "input"))
      (node (ref "IC5") (pin "6") (pinfunction "E_6") (pintype "input"))
      (node (ref "J3") (pin "K2") (pinfunction "K2_K2") (pintype "bidirectional"))
      (node (ref "R86") (pin "2") (pinfunction "2_2") (pintype "passive"))
    )
    (net (code "55") (name "GND") (class "Default")
      (node (ref "C1") (pin "1") (pinfunction "1_1") (pintype "passive"))
      (node (ref "C10") (pin "1") (pinfunction "1_1") (pintype "passive"))
      (node (ref "C144") (pin "1") (pinfunction "1_1") (pintype "passive"))
      (node (ref "C145") (pin "1") (pinfunction "1_1") (pintype "passive"))
      (node (ref "C146") (pin "1") (pinfunction "1_1") (pintype "passive"))
      (node (ref "C147") (pin "1") (pinfunction "1_1") (pintype "passive"))
      (node (ref "C148") (pin "1") (pinfunction "1_1") (pintype "passive"))
      (node (ref "C2") (pin "1") (pinfunction "1_1") (pintype "passive"))
      (node (ref "D12") (pin "1") (pinfunction "GND_1") (pintype "power_in"))
      (node (ref "D27") (pin "2") (pinfunction "GND_2") (pintype "power_in"))
      (node (ref "IC1") (pin "4") (pinfunction "GND_4") (pintype "power_in"))
      (node (ref "IC1") (pin "5") (pinfunction "A2_5") (pintype "input"))
      (node (ref "IC1") (pin "6") (pinfunction "A1_6") (pintype "input"))
      (node (ref "IC1") (pin "7") (pinfunction "A0_7") (pintype "input"))
      (node (ref "IC19") (pin "5") (pinfunction "GND_5") (pintype "power_in"))
      (node (ref "IC2") (pin "2") (pinfunction "VSS_2") (pintype "power_in"))
      (node (ref "IC23") (pin "4") (pinfunction "GND_4") (pintype "power_in"))
      (node (ref "IC29") (pin "5") (pinfunction "GND_5") (pintype "power_in"))
      (node (ref "IC30") (pin "3") (pinfunction "DIN2RIN-_3") (pintype "input"))
      (node (ref "IC30") (pin "4") (pinfunction "GND_4") (pintype "power_in"))
      (node (ref "IC31") (pin "5") (pinfunction "GND_5") (pintype "power_in"))
      (node (ref "IC32") (pin "4") (pinfunction "GND_4") (pintype "power_in"))
      (node (ref "IC36") (pin "4") (pinfunction "GND_4") (pintype "power_in"))
      (node (ref "IC39") (pin "5") (pinfunction "GND_5") (pintype "power_in"))
      (node (ref "IC40") (pin "4") (pinfunction "GND_4") (pintype "power_in"))
      (node (ref "IC41") (pin "5") (pinfunction "GND_5") (pintype "power_in"))
      (node (ref "IC5") (pin "7") (pinfunction "GND_7") (pintype "power_in"))
      (node (ref "J12") (pin "1") (pinfunction "1_1") (pintype "bidirectional"))
      (node (ref "J12") (pin "10") (pinfunction "10_10") (pintype "bidirectional"))
      (node (ref "J12") (pin "13") (pinfunction "13_13") (pintype "bidirectional"))
      (node (ref "J12") (pin "16") (pinfunction "16_16") (pintype "bidirectional"))
      (node (ref "J12") (pin "19") (pinfunction "19_19") (pintype "bidirectional"))
      (node (ref "J12") (pin "22") (pinfunction "22_22") (pintype "bidirectional"))
      (node (ref "J12") (pin "25") (pinfunction "25_25") (pintype "bidirectional"))
      (node (ref "J12") (pin "4") (pinfunction "4_4") (pintype "bidirectional"))
      (node (ref "J12") (pin "7") (pinfunction "7_7") (pintype "bidirectional"))
      (node (ref "J3") (pin "A2") (pinfunction "A2_A2") (pintype "bidirectional"))
      (node (ref "J3") (pin "A4") (pinfunction "A4_A4") (pintype "bidirectional"))
      (node (ref "J3") (pin "A6") (pinfunction "A6_A6") (pintype "bidirectional"))
      (node (ref "J3") (pin "C1") (pinfunction "C1_C1") (pintype "bidirectional"))
      (node (ref "J3") (pin "C5") (pinfunction "C5_C5") (pintype "bidirectional"))
      (node (ref "J3") (pin "D2") (pinfunction "D2_D2") (pintype "bidirectional"))
      (node (ref "J3") (pin "D4") (pinfunction "D4_D4") (pintype "bidirectional"))
      (node (ref "J3") (pin "D6") (pinfunction "D6_D6") (pintype "bidirectional"))
      (node (ref "J3") (pin "F1") (pinfunction "F1_F1") (pintype "bidirectional"))
      (node (ref "J3") (pin "F5") (pinfunction "F5_F5") (pintype "bidirectional"))
      (node (ref "J3") (pin "G2") (pinfunction "G2_G2") (pintype "bidirectional"))
      (node (ref "J3") (pin "G4") (pinfunction "G4_G4") (pintype "bidirectional"))
      (node (ref "J3") (pin "G6") (pinfunction "G6_G6") (pintype "bidirectional"))
      (node (ref "J3") (pin "I1") (pinfunction "I1_I1") (pintype "bidirectional"))
      (node (ref "J3") (pin "I5") (pinfunction "I5_I5") (pintype "bidirectional"))
      (node (ref "J3") (pin "J2") (pinfunction "J2_J2") (pintype "bidirectional"))
      (node (ref "J3") (pin "J4") (pinfunction "J4_J4") (pintype "bidirectional"))
      (node (ref "J3") (pin "J6") (pinfunction "J6_J6") (pintype "bidirectional"))
      (node (ref "J3") (pin "L1") (pinfunction "L1_L1") (pintype "bidirectional"))
      (node (ref "J3") (pin "L5") (pinfunction "L5_L5") (pintype "bidirectional"))
      (node (ref "R195") (pin "1") (pinfunction "1_1") (pintype "passive"))
      (node (ref "R196") (pin "1") (pinfunction "1_1") (pintype "passive"))
      (node (ref "R197") (pin "1") (pinfunction "1_1") (pintype "passive"))
      (node (ref "R86") (pin "1") (pinfunction "1_1") (pintype "passive"))
      (node (ref "T11") (pin "2") (pinfunction "S_2") (pintype "passive"))
    )
    (net (code "56") (name "Net-(IC1-O.S.)") (class "Default")
      (node (ref "IC1") (pin "3") (pinfunction "O.S._3") (pintype "output"))
      (node (ref "R5") (pin "2") (pinfunction "2_2") (pintype "passive"))
      (node (ref "R6") (pin "1") (pinfunction "1_1") (pintype "passive"))
    )
    (net (code "57") (name "Net-(IC19-ROUT1)") (class "Default")
      (node (ref "IC19") (pin "7") (pinfunction "ROUT1_7") (pintype "output"))
      (node (ref "IC23") (pin "2") (pinfunction "DIN1_2") (pintype "input"))
      (node (ref "R108") (pin "2") (pinfunction "2_2") (pintype "passive"))
    )
    (net (code "58") (name "Net-(IC19-ROUT2)") (class "Default")
      (node (ref "IC19") (pin "6") (pinfunction "ROUT2_6") (pintype "output"))
      (node (ref "IC23") (pin "3") (pinfunction "DIN2RIN-_3") (pintype "input"))
      (node (ref "R110") (pin "2") (pinfunction "2_2") (pintype "passive"))
    )
    (net (code "59") (name "Net-(IC29-ROUT1)") (class "Default")
      (node (ref "IC29") (pin "7") (pinfunction "ROUT1_7") (pintype "output"))
      (node (ref "IC36") (pin "2") (pinfunction "DIN1_2") (pintype "input"))
      (node (ref "R112") (pin "2") (pinfunction "2_2") (pintype "passive"))
    )
    (net (code "60") (name "Net-(IC30-DIN1)") (class "Default")
      (node (ref "IC30") (pin "2") (pinfunction "DIN1_2") (pintype "input"))
      (node (ref "IC39") (pin "7") (pinfunction "ROUT1_7") (pintype "output"))
      (node (ref "R113") (pin "2") (pinfunction "2_2") (pintype "passive"))
    )
    (net (code "61") (name "Net-(IC31-ROUT1)") (class "Default")
      (node (ref "IC31") (pin "7") (pinfunction "ROUT1_7") (pintype "output"))
      (node (ref "IC40") (pin "2") (pinfunction "DIN1_2") (pintype "input"))
      (node (ref "R115") (pin "2") (pinfunction "2_2") (pintype "passive"))
    )
    (net (code "62") (name "Net-(IC31-ROUT2)") (class "Default")
      (node (ref "IC31") (pin "6") (pinfunction "ROUT2_6") (pintype "output"))
      (node (ref "IC40") (pin "3") (pinfunction "DIN2RIN-_3") (pintype "input"))
      (node (ref "R117") (pin "2") (pinfunction "2_2") (pintype "passive"))
    )
    (net (code "63") (name "Net-(IC32-DIN1)") (class "Default")
      (node (ref "IC32") (pin "2") (pinfunction "DIN1_2") (pintype "input"))
      (node (ref "IC41") (pin "7") (pinfunction "ROUT1_7") (pintype "output"))
      (node (ref "R118") (pin "2") (pinfunction "2_2") (pintype "passive"))
    )
    (net (code "64") (name "Net-(IC32-DIN2RIN-)") (class "Default")
      (node (ref "IC32") (pin "3") (pinfunction "DIN2RIN-_3") (pintype "input"))
      (node (ref "IC41") (pin "6") (pinfunction "ROUT2_6") (pintype "output"))
      (node (ref "R123") (pin "2") (pinfunction "2_2") (pintype "passive"))
    )
    (net (code "65") (name "Net-(LD1-C)") (class "Default")
      (node (ref "LD1") (pin "1") (pinfunction "C_1") (pintype "passive"))
      (node (ref "R6") (pin "2") (pinfunction "2_2") (pintype "passive"))
    )
    (net (code "66") (name "Net-(T10A-B)") (class "Default")
      (node (ref "R194") (pin "1") (pinfunction "1_1") (pintype "passive"))
      (node (ref "T10") (pin "2") (pinfunction "B_2") (pintype "passive"))
    )
    (net (code "67") (name "Net-(T10A-C)") (class "Default")
      (node (ref "R195") (pin "2") (pinfunction "2_2") (pintype "passive"))
      (node (ref "T10") (pin "6") (pinfunction "C_6") (pintype "passive"))
      (node (ref "T11") (pin "3") (pinfunction "D_3") (pintype "passive"))
      (node (ref "T9") (pin "4") (pinfunction "S_4") (pintype "passive"))
    )
    (net (code "68") (name "Net-(T10B-B)") (class "Default")
      (node (ref "R194") (pin "2") (pinfunction "2_2") (pintype "passive"))
      (node (ref "R196") (pin "2") (pinfunction "2_2") (pintype "passive"))
      (node (ref "T10") (pin "3") (pinfunction "C_3") (pintype "passive"))
      (node (ref "T10") (pin "5") (pinfunction "B_5") (pintype "passive"))
    )
    (net (code "69") (name "P3V3") (class "Default")
      (node (ref "C144") (pin "2") (pinfunction "2_2") (pintype "passive"))
      (node (ref "C145") (pin "2") (pinfunction "2_2") (pintype "passive"))
      (node (ref "C146") (pin "2") (pinfunction "2_2") (pintype "passive"))
      (node (ref "C147") (pin "2") (pinfunction "2_2") (pintype "passive"))
      (node (ref "C148") (pin "2") (pinfunction "2_2") (pintype "passive"))
      (node (ref "D12") (pin "4") (pinfunction "VCC_4") (pintype "power_in"))
      (node (ref "D2") (pin "2") (pinfunction "A_2") (pintype "passive"))
      (node (ref "IC19") (pin "8") (pinfunction "VCC_8") (pintype "power_in"))
      (node (ref "IC23") (pin "1") (pinfunction "VCC_1") (pintype "power_in"))
      (node (ref "IC29") (pin "8") (pinfunction "VCC_8") (pintype "power_in"))
      (node (ref "IC30") (pin "1") (pinfunction "VCC_1") (pintype "power_in"))
      (node (ref "IC31") (pin "8") (pinfunction "VCC_8") (pintype "power_in"))
      (node (ref "IC32") (pin "1") (pinfunction "VCC_1") (pintype "power_in"))
      (node (ref "IC36") (pin "1") (pinfunction "VCC_1") (pintype "power_in"))
      (node (ref "IC39") (pin "8") (pinfunction "VCC_8") (pintype "power_in"))
      (node (ref "IC40") (pin "1") (pinfunction "VCC_1") (pintype "power_in"))
      (node (ref "IC41") (pin "8") (pinfunction "VCC_8") (pintype "power_in"))
      (node (ref "LD1") (pin "2") (pinfunction "A_2") (pintype "passive"))
      (node (ref "R5") (pin "1") (pinfunction "1_1") (pintype "passive"))
    )
    (net (code "70") (name "P3V3_MP") (class "Default")
      (node (ref "C1") (pin "2") (pinfunction "2_2") (pintype "passive"))
      (node (ref "C10") (pin "2") (pinfunction "2_2") (pintype "passive"))
      (node (ref "C2") (pin "2") (pinfunction "2_2") (pintype "passive"))
      (node (ref "D2") (pin "1") (pinfunction "C_1") (pintype "passive"))
      (node (ref "D27") (pin "5") (pinfunction "VBUS_5") (pintype "power_in"))
      (node (ref "IC1") (pin "8") (pinfunction "+VS_8") (pintype "power_in"))
      (node (ref "IC2") (pin "4") (pinfunction "VCC_4") (pintype "power_in"))
      (node (ref "IC5") (pin "14") (pinfunction "VCC_14") (pintype "power_in"))
      (node (ref "J12") (pin "30") (pinfunction "30_30") (pintype "bidirectional"))
      (node (ref "TP3") (pin "1") (pinfunction "1_1") (pintype "bidirectional"))
    )
    (net (code "71") (name "P12V0") (class "Default")
      (node (ref "J3") (pin "A1") (pinfunction "A1_A1") (pintype "bidirectional"))
      (node (ref "J3") (pin "D1") (pinfunction "D1_D1") (pintype "bidirectional"))
      (node (ref "J3") (pin "E1") (pinfunction "E1_E1") (pintype "bidirectional"))
      (node (ref "J3") (pin "G1") (pinfunction "G1_G1") (pintype "bidirectional"))
      (node (ref "J3") (pin "H1") (pinfunction "H1_H1") (pintype "bidirectional"))
      (node (ref "J3") (pin "J1") (pinfunction "J1_J1") (pintype "bidirectional"))
      (node (ref "J3") (pin "K1") (pinfunction "K1_K1") (pintype "bidirectional"))
    )
    (net (code "72") (name "P12V0_EEM") (class "Default")
      (node (ref "J12") (pin "28") (pinfunction "28_28") (pintype "bidirectional"))
      (node (ref "J12") (pin "29") (pinfunction "29_29") (pintype "bidirectional"))
      (node (ref "T10") (pin "4") (pinfunction "E_4") (pintype "passive"))
      (node (ref "T9") (pin "5") (pinfunction "D_5") (pintype "passive"))
      (node (ref "T9") (pin "6") (pinfunction "D_6") (pintype "passive"))
      (node (ref "T9") (pin "7") (pinfunction "D_7") (pintype "passive"))
      (node (ref "T9") (pin "8") (pinfunction "D_8") (pintype "passive"))
    )
    (net (code "73") (name "P12V0_IN") (class "Default")
      (node (ref "T10") (pin "1") (pinfunction "E_1") (pintype "passive"))
      (node (ref "T9") (pin "1") (pinfunction "S_1") (pintype "passive"))
      (node (ref "T9") (pin "2") (pinfunction "S_2") (pintype "passive"))
      (node (ref "T9") (pin "3") (pinfunction "S_3") (pintype "passive"))
    )
    (net (code "74") (name "unconnected-(D12-I{slash}O1-Pad2)") (class "Default")
      (node (ref "D12") (pin "2") (pinfunction "I/O1_2") (pintype "bidirectional"))
    )
    (net (code "75") (name "unconnected-(D27-I{slash}O1-Pad1)") (class "Default")
      (node (ref "D27") (pin "1") (pinfunction "I/O1_1") (pintype "bidirectional+no_connect"))
    )
    (net (code "76") (name "unconnected-(D27-I{slash}O4-Pad6)") (class "Default")
      (node (ref "D27") (pin "6") (pinfunction "I/O4_6") (pintype "bidirectional+no_connect"))
    )
    (net (code "77") (name "unconnected-(IC2-NC-Pad5)") (class "Default")
      (node (ref "IC2") (pin "5") (pinfunction "NC_5") (pintype "passive"))
    )
    (net (code "78") (name "unconnected-(IC29-RIN2+-Pad3)") (class "Default")
      (node (ref "IC29") (pin "3") (pinfunction "RIN2+_3") (pintype "input+no_connect"))
    )
    (net (code "79") (name "unconnected-(IC29-RIN2--Pad4)") (class "Default")
      (node (ref "IC29") (pin "4") (pinfunction "RIN2-_4") (pintype "input+no_connect"))
    )
    (net (code "80") (name "unconnected-(IC29-ROUT2-Pad6)") (class "Default")
      (node (ref "IC29") (pin "6") (pinfunction "ROUT2_6") (pintype "output"))
    )
    (net (code "81") (name "unconnected-(IC30-DOUT+-Pad6)") (class "Default")
      (node (ref "IC30") (pin "6") (pinfunction "DOUT+_6") (pintype "output"))
    )
    (net (code "82") (name "unconnected-(IC30-DOUT--Pad5)") (class "Default")
      (node (ref "IC30") (pin "5") (pinfunction "DOUT-_5") (pintype "output"))
    )
    (net (code "83") (name "unconnected-(IC36-DIN2RIN--Pad3)") (class "Default")
      (node (ref "IC36") (pin "3") (pinfunction "DIN2RIN-_3") (pintype "input+no_connect"))
    )
    (net (code "84") (name "unconnected-(IC36-DOUT+-Pad6)") (class "Default")
      (node (ref "IC36") (pin "6") (pinfunction "DOUT+_6") (pintype "output"))
    )
    (net (code "85") (name "unconnected-(IC36-DOUT--Pad5)") (class "Default")
      (node (ref "IC36") (pin "5") (pinfunction "DOUT-_5") (pintype "output"))
    )
    (net (code "86") (name "unconnected-(IC39-RIN2+-Pad3)") (class "Default")
      (node (ref "IC39") (pin "3") (pinfunction "RIN2+_3") (pintype "input+no_connect"))
    )
    (net (code "87") (name "unconnected-(IC39-RIN2--Pad4)") (class "Default")
      (node (ref "IC39") (pin "4") (pinfunction "RIN2-_4") (pintype "input+no_connect"))
    )
    (net (code "88") (name "unconnected-(IC39-ROUT2-Pad6)") (class "Default")
      (node (ref "IC39") (pin "6") (pinfunction "ROUT2_6") (pintype "output"))
    )
    (net (code "89") (name "unconnected-(J3-PadA5)") (class "Default")
      (node (ref "J3") (pin "A5") (pinfunction "A5_A5") (pintype "bidirectional"))
    )
    (net (code "90") (name "unconnected-(J3-PadB1)") (class "Default")
      (node (ref "J3") (pin "B1") (pinfunction "B1_B1") (pintype "bidirectional+no_connect"))
    )
    (net (code "91") (name "unconnected-(J3-PadB5)") (class "Default")
      (node (ref "J3") (pin "B5") (pinfunction "B5_B5") (pintype "bidirectional"))
    )
    (net (code "92") (name "unconnected-(J3-PadB6)") (class "Default")
      (node (ref "J3") (pin "B6") (pinfunction "B6_B6") (pintype "bidirectional"))
    )
    (net (code "93") (name "unconnected-(J3-PadC6)") (class "Default")
      (node (ref "J3") (pin "C6") (pinfunction "C6_C6") (pintype "bidirectional"))
    )
    (net (code "94") (name "unconnected-(J3-PadD5)") (class "Default")
      (node (ref "J3") (pin "D5") (pinfunction "D5_D5") (pintype "bidirectional"))
    )
    (net (code "95") (name "unconnected-(J3-PadE2)") (class "Default")
      (node (ref "J3") (pin "E2") (pinfunction "E2_E2") (pintype "bidirectional"))
    )
    (net (code "96") (name "unconnected-(J3-PadE4)") (class "Default")
      (node (ref "J3") (pin "E4") (pinfunction "E4_E4") (pintype "bidirectional"))
    )
    (net (code "97") (name "unconnected-(J3-PadE5)") (class "Default")
      (node (ref "J3") (pin "E5") (pinfunction "E5_E5") (pintype "bidirectional"))
    )
    (net (code "98") (name "unconnected-(J3-PadF2)") (class "Default")
      (node (ref "J3") (pin "F2") (pinfunction "F2_F2") (pintype "bidirectional"))
    )
    (net (code "99") (name "unconnected-(J3-PadF4)") (class "Default")
      (node (ref "J3") (pin "F4") (pinfunction "F4_F4") (pintype "bidirectional"))
    )
    (net (code "100") (name "unconnected-(J3-PadG3)") (class "Default")
      (node (ref "J3") (pin "G3") (pinfunction "G3_G3") (pintype "bidirectional"))
    )
    (net (code "101") (name "unconnected-(J3-PadH2)") (class "Default")
      (node (ref "J3") (pin "H2") (pinfunction "H2_H2") (pintype "bidirectional"))
    )
    (net (code "102") (name "unconnected-(J3-PadH3)") (class "Default")
      (node (ref "J3") (pin "H3") (pinfunction "H3_H3") (pintype "bidirectional"))
    )
    (net (code "103") (name "unconnected-(J3-PadH6)") (class "Default")
      (node (ref "J3") (pin "H6") (pinfunction "H6_H6") (pintype "bidirectional"))
    )
    (net (code "104") (name "unconnected-(J3-PadI2)") (class "Default")
      (node (ref "J3") (pin "I2") (pinfunction "I2_I2") (pintype "bidirectional"))
    )
    (net (code "105") (name "unconnected-(J3-PadI6)") (class "Default")
      (node (ref "J3") (pin "I6") (pinfunction "I6_I6") (pintype "bidirectional"))
    )
    (net (code "106") (name "unconnected-(J3-PadJ3)") (class "Default")
      (node (ref "J3") (pin "J3") (pinfunction "J3_J3") (pintype "bidirectional"))
    )
    (net (code "107") (name "unconnected-(J3-PadK3)") (class "Default")
      (node (ref "J3") (pin "K3") (pinfunction "K3_K3") (pintype "bidirectional"))
    )
    (net (code "108") (name "unconnected-(J3-PadK6)") (class "Default")
      (node (ref "J3") (pin "K6") (pinfunction "K6_K6") (pintype "bidirectional"))
    )
    (net (code "109") (name "unconnected-(J3-PadL2)") (class "Default")
      (node (ref "J3") (pin "L2") (pinfunction "L2_L2") (pintype "bidirectional+no_connect"))
    )
    (net (code "110") (name "unconnected-(J3-PadL6)") (class "Default")
      (node (ref "J3") (pin "L6") (pinfunction "L6_L6") (pintype "bidirectional"))
    )
  )
)
